# design.net
KiCad netlist of a schematic drawn in Altium Designer
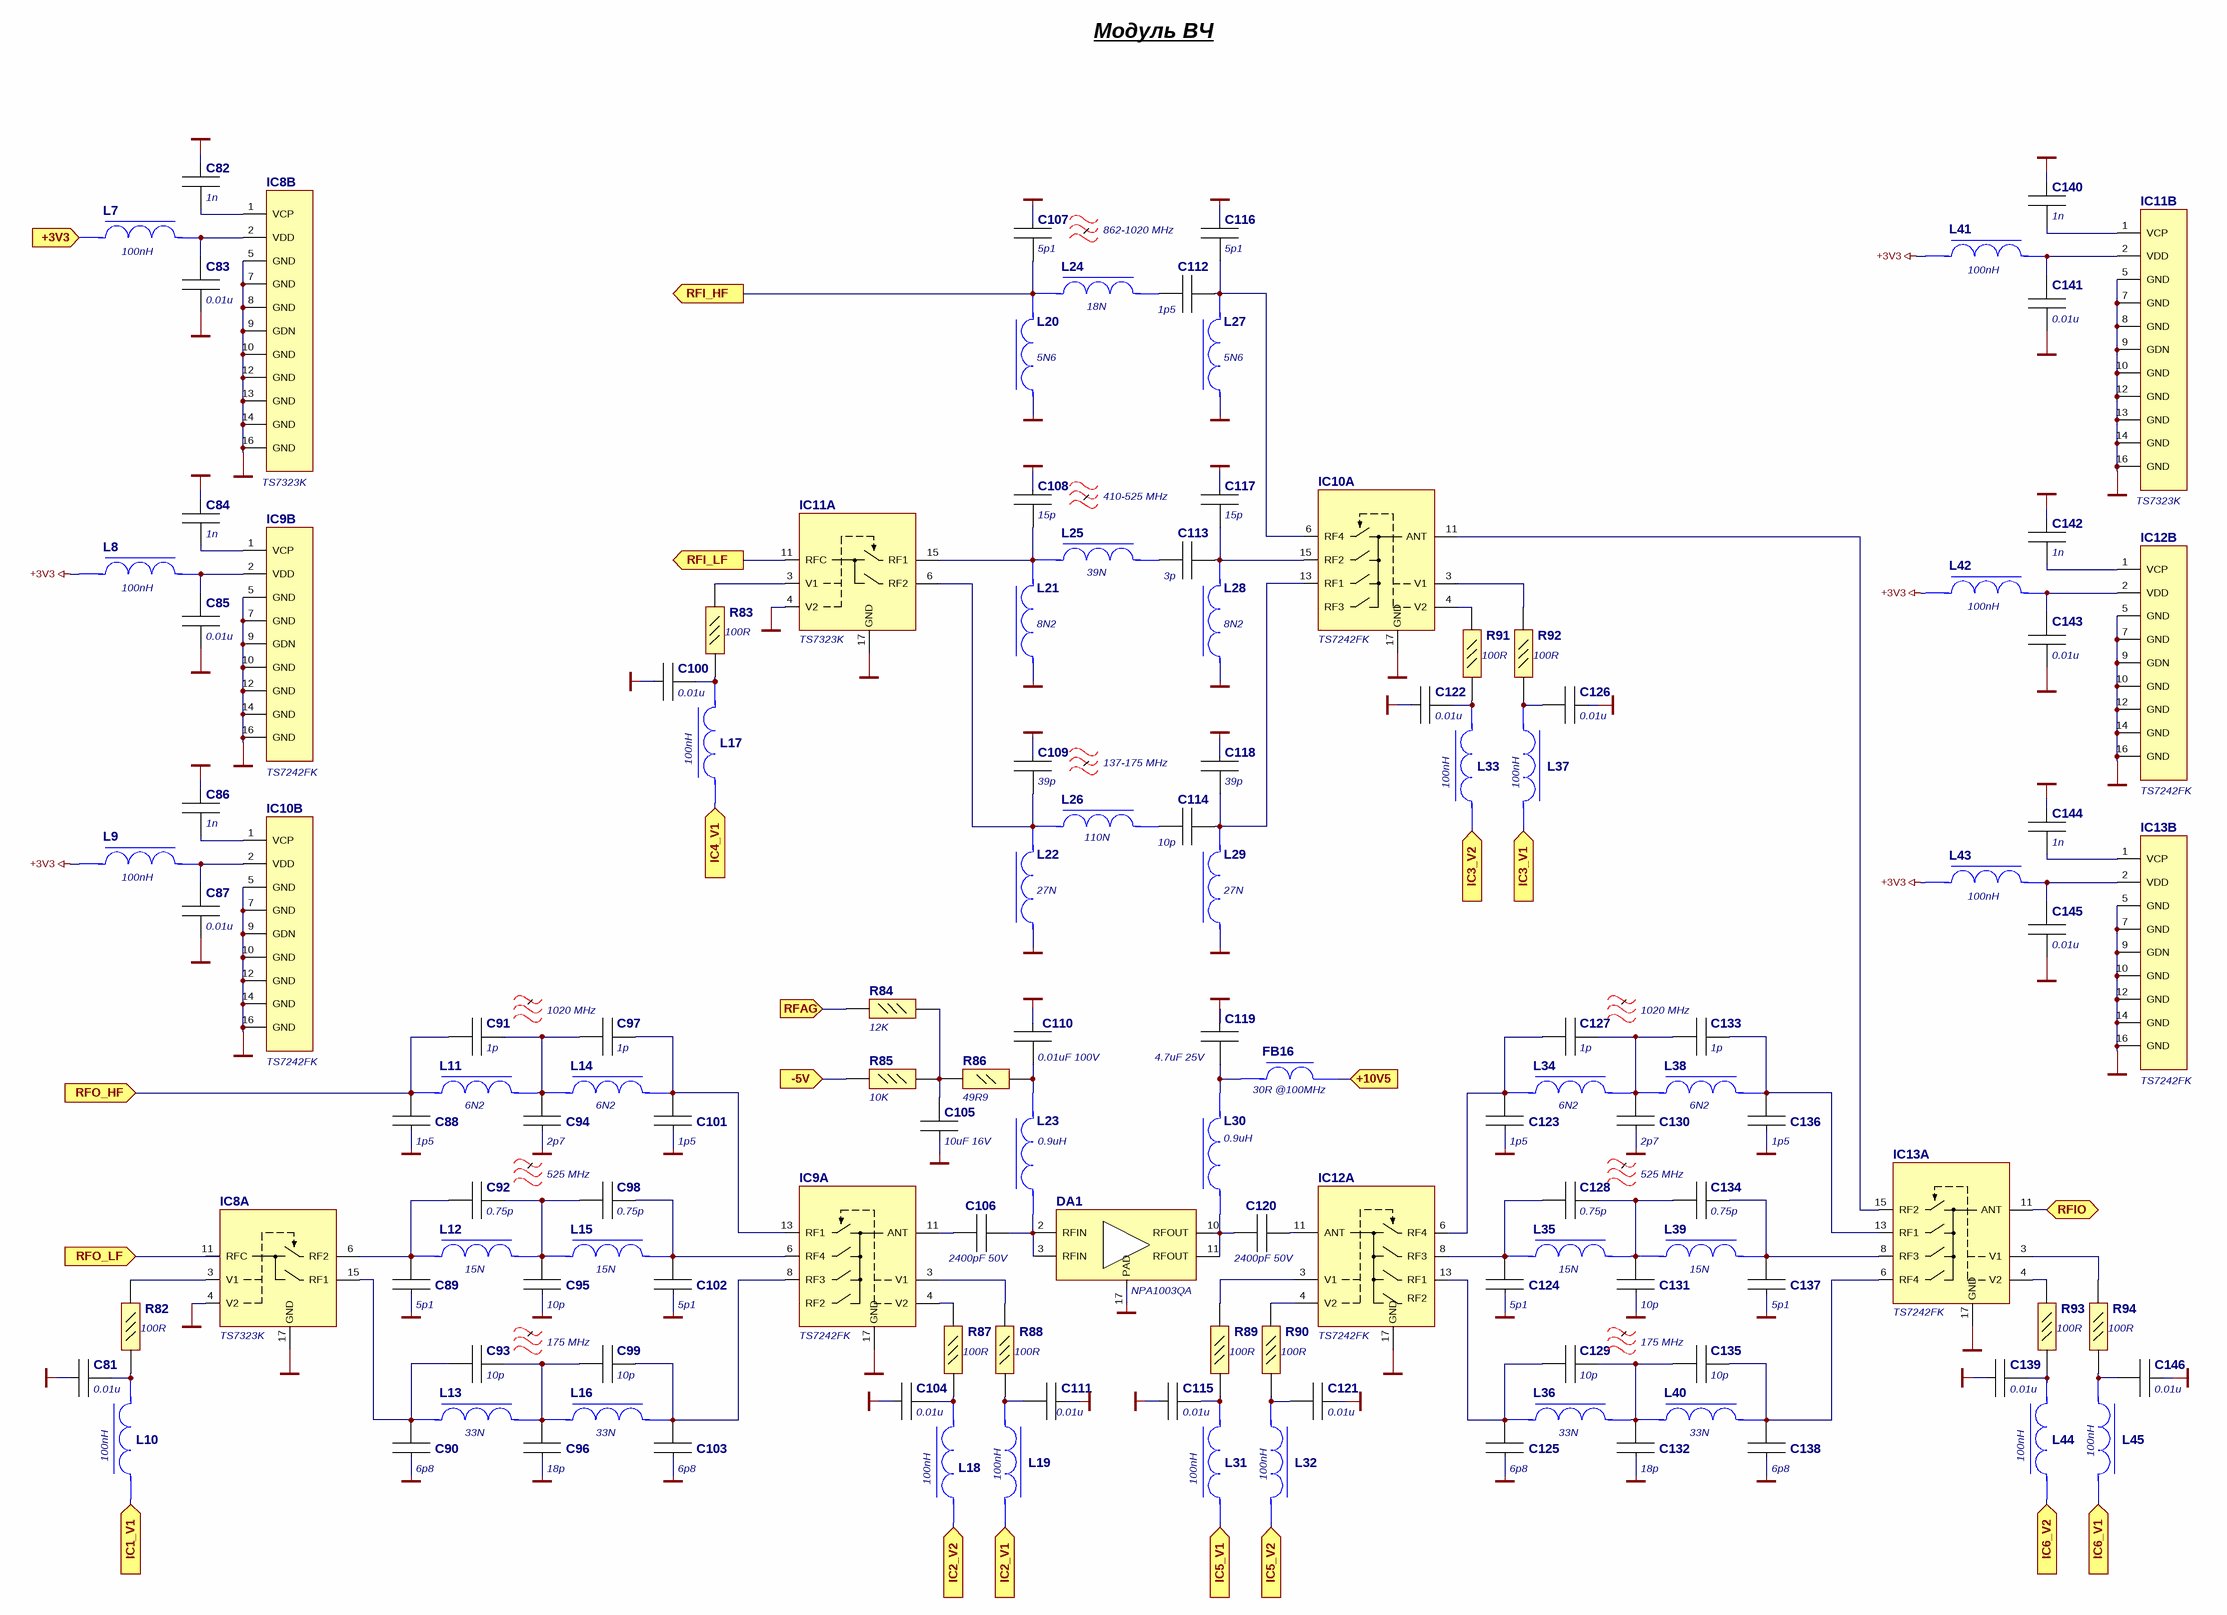
[diagram p0: Модуль ВЧ.SchDoc]

(export (version "E")
  (design (tool "Eeschema 10.0.6"))
  (components
    (comp (ref "C81")
      (value "0.01u")
      (footprint ":CAP0402 100x50x50")
      (description "±5% 35V Ceramic Capacitor C0G, NP0 0402 (1005 Metric)")
      (fields (field (name "MANUFACTURER_PART_NUMBER") "GRM1555CYA103JE01D"))
      (libsource (lib "Capacitors 0402") (part "GRM1555CYA103JE01D"))
    )
    (comp (ref "C82")
      (value "1n")
      (footprint ":CAP0402 100x50x50")
      (description "±5% 50V Ceramic Capacitor C0G, NP0 0402 (1005 Metric)")
      (fields (field (name "MANUFACTURER_PART_NUMBER") "GRM1555C1H102JA01J"))
      (libsource (lib "Capacitors 0402") (part "GRM1555C1H102JA01J"))
    )
    (comp (ref "C83")
      (value "0.01u")
      (footprint ":CAP0402 100x50x50")
      (description "±5% 35V Ceramic Capacitor C0G, NP0 0402 (1005 Metric)")
      (fields (field (name "MANUFACTURER_PART_NUMBER") "GRM1555CYA103JE01D"))
      (libsource (lib "Capacitors 0402") (part "GRM1555CYA103JE01D"))
    )
    (comp (ref "C84")
      (value "1n")
      (footprint ":CAP0402 100x50x50")
      (description "±5% 50V Ceramic Capacitor C0G, NP0 0402 (1005 Metric)")
      (fields (field (name "MANUFACTURER_PART_NUMBER") "GRM1555C1H102JA01J"))
      (libsource (lib "Capacitors 0402") (part "GRM1555C1H102JA01J"))
    )
    (comp (ref "C85")
      (value "0.01u")
      (footprint ":CAP0402 100x50x50")
      (description "±5% 35V Ceramic Capacitor C0G, NP0 0402 (1005 Metric)")
      (fields (field (name "MANUFACTURER_PART_NUMBER") "GRM1555CYA103JE01D"))
      (libsource (lib "Capacitors 0402") (part "GRM1555CYA103JE01D"))
    )
    (comp (ref "C86")
      (value "1n")
      (footprint ":CAP0402 100x50x50")
      (description "±5% 50V Ceramic Capacitor C0G, NP0 0402 (1005 Metric)")
      (fields (field (name "MANUFACTURER_PART_NUMBER") "GRM1555C1H102JA01J"))
      (libsource (lib "Capacitors 0402") (part "GRM1555C1H102JA01J"))
    )
    (comp (ref "C87")
      (value "0.01u")
      (footprint ":CAP0402 100x50x50")
      (description "±5% 35V Ceramic Capacitor C0G, NP0 0402 (1005 Metric)")
      (fields (field (name "MANUFACTURER_PART_NUMBER") "GRM1555CYA103JE01D"))
      (libsource (lib "Capacitors 0402") (part "GRM1555CYA103JE01D"))
    )
    (comp (ref "C88")
      (value "1p5")
      (footprint ":CAP0603 C1608х08")
      (description "Ceramic Capacitor ±0.1pF 250V C0G, NP0 0603 (1608 Metric)")
      (fields (field (name "MANUFACTURER_PART_NUMBER") "GQM1875C2E1R5BB12D"))
      (libsource (lib "Capacitors 0603 ±0.1pF 250V NP0") (part "GQM1875C2E1R5BB12D"))
    )
    (comp (ref "C89")
      (value "5p1")
      (footprint ":CAP0603 C1608х08")
      (description "Ceramic Capacitor ±0.1pF 250V C0G, NP0 0603 (1608 Metric)")
      (fields (field (name "MANUFACTURER_PART_NUMBER") "GQM1875C2E5R1BB12D"))
      (libsource (lib "Capacitors 0603 ±0.1pF 250V NP0") (part "GQM1875C2E5R1BB12D"))
    )
    (comp (ref "C90")
      (value "6p8")
      (footprint ":CAP0603 C1608х08")
      (description "Ceramic Capacitor ±0.1pF 250V C0G, NP0 0603 (1608 Metric)")
      (fields (field (name "MANUFACTURER_PART_NUMBER") "GQM1875C2E6R8BB12D"))
      (libsource (lib "Capacitors 0603 ±0.1pF 250V NP0") (part "GQM1875C2E6R8BB12D"))
    )
    (comp (ref "C91")
      (value "1p")
      (footprint ":CAP0603 C1608х08")
      (description "Ceramic Capacitor ±0.1pF 250V C0G, NP0 0603 (1608 Metric)")
      (fields (field (name "MANUFACTURER_PART_NUMBER") "GQM1875C2E1R0BB12D"))
      (libsource (lib "Capacitors 0603 ±0.1pF 250V NP0") (part "GQM1875C2E1R0BB12D"))
    )
    (comp (ref "C92")
      (value "0.75p")
      (footprint ":CAP0603 C1608х08")
      (description "Ceramic Capacitor ±0.1pF 250V C0G, NP0 0603 (1608 Metric)")
      (fields (field (name "MANUFACTURER_PART_NUMBER") "GQM1875C2ER75BB12D"))
      (libsource (lib "Capacitors 0603 ±0.1pF 250V NP0") (part "GQM1875C2ER75BB12D"))
    )
    (comp (ref "C93")
      (value "10p")
      (footprint ":CAP0603 C1608х08")
      (description "Ceramic Capacitor ±1% 250V C0G, NP0 0603 (1608 Metric)")
      (fields (field (name "MANUFACTURER_PART_NUMBER") "GQM1875C2E100FB12D"))
      (libsource (lib "Capacitors 0603 1% 250V NP0") (part "GQM1875C2E100FB12D"))
    )
    (comp (ref "C94")
      (value "2p7")
      (footprint ":CAP0603 C1608х08")
      (description "Ceramic Capacitor ±0.1pF 250V C0G, NP0 0603 (1608 Metric)")
      (fields (field (name "MANUFACTURER_PART_NUMBER") "GQM1875C2E2R7BB12D"))
      (libsource (lib "Capacitors 0603 ±0.1pF 250V NP0") (part "GQM1875C2E2R7BB12D"))
    )
    (comp (ref "C95")
      (value "10p")
      (footprint ":CAP0603 C1608х08")
      (description "Ceramic Capacitor ±1% 250V C0G, NP0 0603 (1608 Metric)")
      (fields (field (name "MANUFACTURER_PART_NUMBER") "GQM1875C2E100FB12D"))
      (libsource (lib "Capacitors 0603 1% 250V NP0") (part "GQM1875C2E100FB12D"))
    )
    (comp (ref "C96")
      (value "18p")
      (footprint ":CAP0603 C1608х08")
      (description "Ceramic Capacitor ±1% 250V C0G, NP0 0603 (1608 Metric)")
      (fields (field (name "MANUFACTURER_PART_NUMBER") "GQM1875C2E180FB12D"))
      (libsource (lib "Capacitors 0603 1% 250V NP0") (part "GQM1875C2E180FB12D"))
    )
    (comp (ref "C97")
      (value "1p")
      (footprint ":CAP0603 C1608х08")
      (description "Ceramic Capacitor ±0.1pF 250V C0G, NP0 0603 (1608 Metric)")
      (fields (field (name "MANUFACTURER_PART_NUMBER") "GQM1875C2E1R0BB12D"))
      (libsource (lib "Capacitors 0603 ±0.1pF 250V NP0") (part "GQM1875C2E1R0BB12D"))
    )
    (comp (ref "C98")
      (value "0.75p")
      (footprint ":CAP0603 C1608х08")
      (description "Ceramic Capacitor ±0.1pF 250V C0G, NP0 0603 (1608 Metric)")
      (fields (field (name "MANUFACTURER_PART_NUMBER") "GQM1875C2ER75BB12D"))
      (libsource (lib "Capacitors 0603 ±0.1pF 250V NP0") (part "GQM1875C2ER75BB12D"))
    )
    (comp (ref "C99")
      (value "10p")
      (footprint ":CAP0603 C1608х08")
      (description "Ceramic Capacitor ±1% 250V C0G, NP0 0603 (1608 Metric)")
      (fields (field (name "MANUFACTURER_PART_NUMBER") "GQM1875C2E100FB12D"))
      (libsource (lib "Capacitors 0603 1% 250V NP0") (part "GQM1875C2E100FB12D"))
    )
    (comp (ref "C100")
      (value "0.01u")
      (footprint ":CAP0402 100x50x50")
      (description "±5% 35V Ceramic Capacitor C0G, NP0 0402 (1005 Metric)")
      (fields (field (name "MANUFACTURER_PART_NUMBER") "GRM1555CYA103JE01D"))
      (libsource (lib "Capacitors 0402") (part "GRM1555CYA103JE01D"))
    )
    (comp (ref "C101")
      (value "1p5")
      (footprint ":CAP0603 C1608х08")
      (description "Ceramic Capacitor ±0.1pF 250V C0G, NP0 0603 (1608 Metric)")
      (fields (field (name "MANUFACTURER_PART_NUMBER") "GQM1875C2E1R5BB12D"))
      (libsource (lib "Capacitors 0603 ±0.1pF 250V NP0") (part "GQM1875C2E1R5BB12D"))
    )
    (comp (ref "C102")
      (value "5p1")
      (footprint ":CAP0603 C1608х08")
      (description "Ceramic Capacitor ±0.1pF 250V C0G, NP0 0603 (1608 Metric)")
      (fields (field (name "MANUFACTURER_PART_NUMBER") "GQM1875C2E5R1BB12D"))
      (libsource (lib "Capacitors 0603 ±0.1pF 250V NP0") (part "GQM1875C2E5R1BB12D"))
    )
    (comp (ref "C103")
      (value "6p8")
      (footprint ":CAP0603 C1608х08")
      (description "Ceramic Capacitor ±0.1pF 250V C0G, NP0 0603 (1608 Metric)")
      (fields (field (name "MANUFACTURER_PART_NUMBER") "GQM1875C2E6R8BB12D"))
      (libsource (lib "Capacitors 0603 ±0.1pF 250V NP0") (part "GQM1875C2E6R8BB12D"))
    )
    (comp (ref "C104")
      (value "0.01u")
      (footprint ":CAP0402 100x50x50")
      (description "±5% 35V Ceramic Capacitor C0G, NP0 0402 (1005 Metric)")
      (fields (field (name "MANUFACTURER_PART_NUMBER") "GRM1555CYA103JE01D"))
      (libsource (lib "Capacitors 0402") (part "GRM1555CYA103JE01D"))
    )
    (comp (ref "C105")
      (value "10uF 16V")
      (footprint ":CAP0805 C2012X125")
      (description "CAP CER 10uF 16V X5R 0805")
      (fields
        (field (name "MANUFACTURER_PART_NUMBER") "C2012X5R1C106M085AC")
        (field (name "MOUSER PART NUMBER") "810-C2012X5R1C106M-2")
      )
      (libsource (lib "Capacitors 0805") (part "C2012X5R1C106M085AC"))
    )
    (comp (ref "C106")
      (value "2400pF 50V")
      (footprint ":CAP0805 C2012X125")
      (description "2400pF 50V Ceramic Capacitor 0805 (2012 Metric)")
      (fields (field (name "MANUFACTURER_PART_NUMBER") "C08BL242X-5UN-X0T"))
      (libsource (lib "Capacitors 0805") (part "C08BL242X-5UN-X0T"))
    )
    (comp (ref "C107")
      (value "5p1")
      (footprint ":CAP0603 C1608х08")
      (description "Ceramic Capacitor ±0.1pF 250V C0G, NP0 0603 (1608 Metric)")
      (fields (field (name "MANUFACTURER_PART_NUMBER") "GQM1875C2E5R1BB12D"))
      (libsource (lib "Capacitors 0603 ±0.1pF 250V NP0") (part "GQM1875C2E5R1BB12D"))
    )
    (comp (ref "C108")
      (value "15p")
      (footprint ":CAP0603 C1608х08")
      (description "Ceramic Capacitor ±1% 250V C0G, NP0 0603 (1608 Metric)")
      (fields (field (name "MANUFACTURER_PART_NUMBER") "GQM1875C2E150FB12D"))
      (libsource (lib "Capacitors 0603 1% 250V NP0") (part "GQM1875C2E150FB12D"))
    )
    (comp (ref "C109")
      (value "39p")
      (footprint ":CAP0603 C1608х08")
      (description "Ceramic Capacitor ±1% 250V C0G, NP0 0603 (1608 Metric)")
      (fields (field (name "MANUFACTURER_PART_NUMBER") "GQM1875C2E390FB12D"))
      (libsource (lib "Capacitors 0603 1% 250V NP0") (part "GQM1875C2E390FB12D"))
    )
    (comp (ref "C110")
      (value "0.01uF 100V")
      (footprint ":CAP0603 C1608х08")
      (description "CAP CER 0.01uF 100V X7R 0603")
      (fields
        (field (name "MANUFACTURER_PART_NUMBER") "06031C103JAT2A")
        (field (name "MOUSER PART NUMBER") "581-06031C103J")
      )
      (libsource (lib "Capacitors 0603") (part "06031C103JAT2A"))
    )
    (comp (ref "C111")
      (value "0.01u")
      (footprint ":CAP0402 100x50x50")
      (description "±5% 35V Ceramic Capacitor C0G, NP0 0402 (1005 Metric)")
      (fields (field (name "MANUFACTURER_PART_NUMBER") "GRM1555CYA103JE01D"))
      (libsource (lib "Capacitors 0402") (part "GRM1555CYA103JE01D"))
    )
    (comp (ref "C112")
      (value "1p5")
      (footprint ":CAP0603 C1608х08")
      (description "Ceramic Capacitor ±0.1pF 250V C0G, NP0 0603 (1608 Metric)")
      (fields (field (name "MANUFACTURER_PART_NUMBER") "GQM1875C2E1R5BB12D"))
      (libsource (lib "Capacitors 0603 ±0.1pF 250V NP0") (part "GQM1875C2E1R5BB12D"))
    )
    (comp (ref "C113")
      (value "3p")
      (footprint ":CAP0603 C1608х08")
      (description "Ceramic Capacitor ±0.1pF 250V C0G, NP0 0603 (1608 Metric)")
      (fields (field (name "MANUFACTURER_PART_NUMBER") "GQM1875C2E3R0BB12D"))
      (libsource (lib "Capacitors 0603 ±0.1pF 250V NP0") (part "GQM1875C2E3R0BB12D"))
    )
    (comp (ref "C114")
      (value "10p")
      (footprint ":CAP0603 C1608х08")
      (description "Ceramic Capacitor ±1% 250V C0G, NP0 0603 (1608 Metric)")
      (fields (field (name "MANUFACTURER_PART_NUMBER") "GQM1875C2E100FB12D"))
      (libsource (lib "Capacitors 0603 1% 250V NP0") (part "GQM1875C2E100FB12D"))
    )
    (comp (ref "C115")
      (value "0.01u")
      (footprint ":CAP0402 100x50x50")
      (description "±5% 35V Ceramic Capacitor C0G, NP0 0402 (1005 Metric)")
      (fields (field (name "MANUFACTURER_PART_NUMBER") "GRM1555CYA103JE01D"))
      (libsource (lib "Capacitors 0402") (part "GRM1555CYA103JE01D"))
    )
    (comp (ref "C116")
      (value "5p1")
      (footprint ":CAP0603 C1608х08")
      (description "Ceramic Capacitor ±0.1pF 250V C0G, NP0 0603 (1608 Metric)")
      (fields (field (name "MANUFACTURER_PART_NUMBER") "GQM1875C2E5R1BB12D"))
      (libsource (lib "Capacitors 0603 ±0.1pF 250V NP0") (part "GQM1875C2E5R1BB12D"))
    )
    (comp (ref "C117")
      (value "15p")
      (footprint ":CAP0603 C1608х08")
      (description "Ceramic Capacitor ±1% 250V C0G, NP0 0603 (1608 Metric)")
      (fields (field (name "MANUFACTURER_PART_NUMBER") "GQM1875C2E150FB12D"))
      (libsource (lib "Capacitors 0603 1% 250V NP0") (part "GQM1875C2E150FB12D"))
    )
    (comp (ref "C118")
      (value "39p")
      (footprint ":CAP0603 C1608х08")
      (description "Ceramic Capacitor ±1% 250V C0G, NP0 0603 (1608 Metric)")
      (fields (field (name "MANUFACTURER_PART_NUMBER") "GQM1875C2E390FB12D"))
      (libsource (lib "Capacitors 0603 1% 250V NP0") (part "GQM1875C2E390FB12D"))
    )
    (comp (ref "C119")
      (value "4.7uF 25V")
      (footprint ":CAP0805 C2012X125")
      (description "CAP CER 4.7uF 25V X7R 0805")
      (fields (field (name "MANUFACTURER_PART_NUMBER") "GRM21BZ71E475KE15L"))
      (libsource (lib "Capacitors 0805") (part "GRM21BZ71E475KE15L"))
    )
    (comp (ref "C120")
      (value "2400pF 50V")
      (footprint ":CAP0805 C2012X125")
      (description "2400pF 50V Ceramic Capacitor 0805 (2012 Metric)")
      (fields (field (name "MANUFACTURER_PART_NUMBER") "C08BL242X-5UN-X0T"))
      (libsource (lib "Capacitors 0805") (part "C08BL242X-5UN-X0T"))
    )
    (comp (ref "C121")
      (value "0.01u")
      (footprint ":CAP0402 100x50x50")
      (description "±5% 35V Ceramic Capacitor C0G, NP0 0402 (1005 Metric)")
      (fields (field (name "MANUFACTURER_PART_NUMBER") "GRM1555CYA103JE01D"))
      (libsource (lib "Capacitors 0402") (part "GRM1555CYA103JE01D"))
    )
    (comp (ref "C122")
      (value "0.01u")
      (footprint ":CAP0402 100x50x50")
      (description "±5% 35V Ceramic Capacitor C0G, NP0 0402 (1005 Metric)")
      (fields (field (name "MANUFACTURER_PART_NUMBER") "GRM1555CYA103JE01D"))
      (libsource (lib "Capacitors 0402") (part "GRM1555CYA103JE01D"))
    )
    (comp (ref "C123")
      (value "1p5")
      (footprint ":CAP0603 C1608х08")
      (description "Ceramic Capacitor ±0.1pF 250V C0G, NP0 0603 (1608 Metric)")
      (fields (field (name "MANUFACTURER_PART_NUMBER") "GQM1875C2E1R5BB12D"))
      (libsource (lib "Capacitors 0603 ±0.1pF 250V NP0") (part "GQM1875C2E1R5BB12D"))
    )
    (comp (ref "C124")
      (value "5p1")
      (footprint ":CAP0603 C1608х08")
      (description "Ceramic Capacitor ±0.1pF 250V C0G, NP0 0603 (1608 Metric)")
      (fields (field (name "MANUFACTURER_PART_NUMBER") "GQM1875C2E5R1BB12D"))
      (libsource (lib "Capacitors 0603 ±0.1pF 250V NP0") (part "GQM1875C2E5R1BB12D"))
    )
    (comp (ref "C125")
      (value "6p8")
      (footprint ":CAP0603 C1608х08")
      (description "Ceramic Capacitor ±0.1pF 250V C0G, NP0 0603 (1608 Metric)")
      (fields (field (name "MANUFACTURER_PART_NUMBER") "GQM1875C2E6R8BB12D"))
      (libsource (lib "Capacitors 0603 ±0.1pF 250V NP0") (part "GQM1875C2E6R8BB12D"))
    )
    (comp (ref "C126")
      (value "0.01u")
      (footprint ":CAP0402 100x50x50")
      (description "±5% 35V Ceramic Capacitor C0G, NP0 0402 (1005 Metric)")
      (fields (field (name "MANUFACTURER_PART_NUMBER") "GRM1555CYA103JE01D"))
      (libsource (lib "Capacitors 0402") (part "GRM1555CYA103JE01D"))
    )
    (comp (ref "C127")
      (value "1p")
      (footprint ":CAP0603 C1608х08")
      (description "Ceramic Capacitor ±0.1pF 250V C0G, NP0 0603 (1608 Metric)")
      (fields (field (name "MANUFACTURER_PART_NUMBER") "GQM1875C2E1R0BB12D"))
      (libsource (lib "Capacitors 0603 ±0.1pF 250V NP0") (part "GQM1875C2E1R0BB12D"))
    )
    (comp (ref "C128")
      (value "0.75p")
      (footprint ":CAP0603 C1608х08")
      (description "Ceramic Capacitor ±0.1pF 250V C0G, NP0 0603 (1608 Metric)")
      (fields (field (name "MANUFACTURER_PART_NUMBER") "GQM1875C2ER75BB12D"))
      (libsource (lib "Capacitors 0603 ±0.1pF 250V NP0") (part "GQM1875C2ER75BB12D"))
    )
    (comp (ref "C129")
      (value "10p")
      (footprint ":CAP0603 C1608х08")
      (description "Ceramic Capacitor ±1% 250V C0G, NP0 0603 (1608 Metric)")
      (fields (field (name "MANUFACTURER_PART_NUMBER") "GQM1875C2E100FB12D"))
      (libsource (lib "Capacitors 0603 1% 250V NP0") (part "GQM1875C2E100FB12D"))
    )
    (comp (ref "C130")
      (value "2p7")
      (footprint ":CAP0603 C1608х08")
      (description "Ceramic Capacitor ±0.1pF 250V C0G, NP0 0603 (1608 Metric)")
      (fields (field (name "MANUFACTURER_PART_NUMBER") "GQM1875C2E2R7BB12D"))
      (libsource (lib "Capacitors 0603 ±0.1pF 250V NP0") (part "GQM1875C2E2R7BB12D"))
    )
    (comp (ref "C131")
      (value "10p")
      (footprint ":CAP0603 C1608х08")
      (description "Ceramic Capacitor ±1% 250V C0G, NP0 0603 (1608 Metric)")
      (fields (field (name "MANUFACTURER_PART_NUMBER") "GQM1875C2E100FB12D"))
      (libsource (lib "Capacitors 0603 1% 250V NP0") (part "GQM1875C2E100FB12D"))
    )
    (comp (ref "C132")
      (value "18p")
      (footprint ":CAP0603 C1608х08")
      (description "Ceramic Capacitor ±1% 250V C0G, NP0 0603 (1608 Metric)")
      (fields (field (name "MANUFACTURER_PART_NUMBER") "GQM1875C2E180FB12D"))
      (libsource (lib "Capacitors 0603 1% 250V NP0") (part "GQM1875C2E180FB12D"))
    )
    (comp (ref "C133")
      (value "1p")
      (footprint ":CAP0603 C1608х08")
      (description "Ceramic Capacitor ±0.1pF 250V C0G, NP0 0603 (1608 Metric)")
      (fields (field (name "MANUFACTURER_PART_NUMBER") "GQM1875C2E1R0BB12D"))
      (libsource (lib "Capacitors 0603 ±0.1pF 250V NP0") (part "GQM1875C2E1R0BB12D"))
    )
    (comp (ref "C134")
      (value "0.75p")
      (footprint ":CAP0603 C1608х08")
      (description "Ceramic Capacitor ±0.1pF 250V C0G, NP0 0603 (1608 Metric)")
      (fields (field (name "MANUFACTURER_PART_NUMBER") "GQM1875C2ER75BB12D"))
      (libsource (lib "Capacitors 0603 ±0.1pF 250V NP0") (part "GQM1875C2ER75BB12D"))
    )
    (comp (ref "C135")
      (value "10p")
      (footprint ":CAP0603 C1608х08")
      (description "Ceramic Capacitor ±1% 250V C0G, NP0 0603 (1608 Metric)")
      (fields (field (name "MANUFACTURER_PART_NUMBER") "GQM1875C2E100FB12D"))
      (libsource (lib "Capacitors 0603 1% 250V NP0") (part "GQM1875C2E100FB12D"))
    )
    (comp (ref "C136")
      (value "1p5")
      (footprint ":CAP0603 C1608х08")
      (description "Ceramic Capacitor ±0.1pF 250V C0G, NP0 0603 (1608 Metric)")
      (fields (field (name "MANUFACTURER_PART_NUMBER") "GQM1875C2E1R5BB12D"))
      (libsource (lib "Capacitors 0603 ±0.1pF 250V NP0") (part "GQM1875C2E1R5BB12D"))
    )
    (comp (ref "C137")
      (value "5p1")
      (footprint ":CAP0603 C1608х08")
      (description "Ceramic Capacitor ±0.1pF 250V C0G, NP0 0603 (1608 Metric)")
      (fields (field (name "MANUFACTURER_PART_NUMBER") "GQM1875C2E5R1BB12D"))
      (libsource (lib "Capacitors 0603 ±0.1pF 250V NP0") (part "GQM1875C2E5R1BB12D"))
    )
    (comp (ref "C138")
      (value "6p8")
      (footprint ":CAP0603 C1608х08")
      (description "Ceramic Capacitor ±0.1pF 250V C0G, NP0 0603 (1608 Metric)")
      (fields (field (name "MANUFACTURER_PART_NUMBER") "GQM1875C2E6R8BB12D"))
      (libsource (lib "Capacitors 0603 ±0.1pF 250V NP0") (part "GQM1875C2E6R8BB12D"))
    )
    (comp (ref "C139")
      (value "0.01u")
      (footprint ":CAP0402 100x50x50")
      (description "±5% 35V Ceramic Capacitor C0G, NP0 0402 (1005 Metric)")
      (fields (field (name "MANUFACTURER_PART_NUMBER") "GRM1555CYA103JE01D"))
      (libsource (lib "Capacitors 0402") (part "GRM1555CYA103JE01D"))
    )
    (comp (ref "C140")
      (value "1n")
      (footprint ":CAP0402 100x50x50")
      (description "±5% 50V Ceramic Capacitor C0G, NP0 0402 (1005 Metric)")
      (fields (field (name "MANUFACTURER_PART_NUMBER") "GRM1555C1H102JA01J"))
      (libsource (lib "Capacitors 0402") (part "GRM1555C1H102JA01J"))
    )
    (comp (ref "C141")
      (value "0.01u")
      (footprint ":CAP0402 100x50x50")
      (description "±5% 35V Ceramic Capacitor C0G, NP0 0402 (1005 Metric)")
      (fields (field (name "MANUFACTURER_PART_NUMBER") "GRM1555CYA103JE01D"))
      (libsource (lib "Capacitors 0402") (part "GRM1555CYA103JE01D"))
    )
    (comp (ref "C142")
      (value "1n")
      (footprint ":CAP0402 100x50x50")
      (description "±5% 50V Ceramic Capacitor C0G, NP0 0402 (1005 Metric)")
      (fields (field (name "MANUFACTURER_PART_NUMBER") "GRM1555C1H102JA01J"))
      (libsource (lib "Capacitors 0402") (part "GRM1555C1H102JA01J"))
    )
    (comp (ref "C143")
      (value "0.01u")
      (footprint ":CAP0402 100x50x50")
      (description "±5% 35V Ceramic Capacitor C0G, NP0 0402 (1005 Metric)")
      (fields (field (name "MANUFACTURER_PART_NUMBER") "GRM1555CYA103JE01D"))
      (libsource (lib "Capacitors 0402") (part "GRM1555CYA103JE01D"))
    )
    (comp (ref "C144")
      (value "1n")
      (footprint ":CAP0402 100x50x50")
      (description "±5% 50V Ceramic Capacitor C0G, NP0 0402 (1005 Metric)")
      (fields (field (name "MANUFACTURER_PART_NUMBER") "GRM1555C1H102JA01J"))
      (libsource (lib "Capacitors 0402") (part "GRM1555C1H102JA01J"))
    )
    (comp (ref "C145")
      (value "0.01u")
      (footprint ":CAP0402 100x50x50")
      (description "±5% 35V Ceramic Capacitor C0G, NP0 0402 (1005 Metric)")
      (fields (field (name "MANUFACTURER_PART_NUMBER") "GRM1555CYA103JE01D"))
      (libsource (lib "Capacitors 0402") (part "GRM1555CYA103JE01D"))
    )
    (comp (ref "C146")
      (value "0.01u")
      (footprint ":CAP0402 100x50x50")
      (description "±5% 35V Ceramic Capacitor C0G, NP0 0402 (1005 Metric)")
      (fields (field (name "MANUFACTURER_PART_NUMBER") "GRM1555CYA103JE01D"))
      (libsource (lib "Capacitors 0402") (part "GRM1555CYA103JE01D"))
    )
    (comp (ref "DA1")
      (value "NPA1003QA")
      (footprint ":QFN16 P400X400X95-17N-D")
      (description "GaN 20 - 1500 MHz Power Amplifier 16dB 5W")
      (fields (field (name "MOUSER PART NUMBER") "937-NPA1003QA"))
      (libsource (lib "Analog ICs") (part "NPA1003QA"))
    )
    (comp (ref "FB16")
      (value "30R @100MHz")
      (footprint ":FER BLM18SP300SN1D")
      (description "30 Ohms @ 100MHz 1 Power Line Ferrite Bead 0603 (1608 Metric) 6A 8mOhm")
      (fields
        (field (name "MANUFACTURER_PART_NUMBER") "BLM18SP300SN1D")
        (field (name "MOUSER PART NUMBER") "81-BLM18SP300SN1D")
      )
      (libsource (lib "Ferrite Bead") (part "BLM18SP300SN1D"))
    )
    (comp (ref "IC8")
      (value "TS7323K")
      (footprint ":QFN16 P300X300X80-17N-D")
      (description "SPDT Switch 1MHz to 1GHz")
      (fields (field (name "MANUFACTURER_PART_NUMBER") "TS7323KMTRPBF"))
      (libsource (lib "") (part "TS7323K_1"))
    )
    (comp (ref "IC9")
      (value "TS7242FK")
      (footprint ":QFN16 P300X300X80-17N-D")
      (description "SP4T Switch 10MHz to 3GHz")
      (fields (field (name "MANUFACTURER_PART_NUMBER") "TS7242FKMTRPBF"))
      (libsource (lib "") (part "TS7242FK_1"))
    )
    (comp (ref "IC10")
      (value "TS7242FK")
      (footprint ":QFN16 P300X300X80-17N-D")
      (description "SP4T Switch 10MHz to 3GHz")
      (fields (field (name "MANUFACTURER_PART_NUMBER") "TS7242FKMTRPBF"))
      (libsource (lib "") (part "TS7242FK_4"))
    )
    (comp (ref "IC11")
      (value "TS7323K")
      (footprint ":QFN16 P300X300X80-17N-D")
      (description "SPDT Switch 1MHz to 1GHz")
      (fields (field (name "MANUFACTURER_PART_NUMBER") "TS7323KMTRPBF"))
      (libsource (lib "") (part "TS7323K_1"))
    )
    (comp (ref "IC12")
      (value "TS7242FK")
      (footprint ":QFN16 P300X300X80-17N-D")
      (description "SP4T Switch 10MHz to 3GHz")
      (fields (field (name "MANUFACTURER_PART_NUMBER") "TS7242FKMTRPBF"))
      (libsource (lib "") (part "TS7242FK_3"))
    )
    (comp (ref "IC13")
      (value "TS7242FK")
      (footprint ":QFN16 P300X300X80-17N-D")
      (description "SP4T Switch 10MHz to 3GHz")
      (fields (field (name "MANUFACTURER_PART_NUMBER") "TS7242FKMTRPBF"))
      (libsource (lib "") (part "TS7242FK_2"))
    )
    (comp (ref "L7")
      (value "100nH")
      (footprint ":IND 0402")
      (description "Unshielded Multilayer Inductor 0402 5%")
      (fields (field (name "MANUFACTURER_PART_NUMBER") "LQG15HNR10J02D"))
      (libsource (lib "Inductance 0402") (part "LQG15HNR10J02D"))
    )
    (comp (ref "L8")
      (value "100nH")
      (footprint ":IND 0402")
      (description "Unshielded Multilayer Inductor 0402 5%")
      (fields (field (name "MANUFACTURER_PART_NUMBER") "LQG15HNR10J02D"))
      (libsource (lib "Inductance 0402") (part "LQG15HNR10J02D"))
    )
    (comp (ref "L9")
      (value "100nH")
      (footprint ":IND 0402")
      (description "Unshielded Multilayer Inductor 0402 5%")
      (fields (field (name "MANUFACTURER_PART_NUMBER") "LQG15HNR10J02D"))
      (libsource (lib "Inductance 0402") (part "LQG15HNR10J02D"))
    )
    (comp (ref "L10")
      (value "100nH")
      (footprint ":IND 0402")
      (description "Unshielded Multilayer Inductor 0402 5%")
      (fields (field (name "MANUFACTURER_PART_NUMBER") "LQG15HNR10J02D"))
      (libsource (lib "Inductance 0402") (part "LQG15HNR10J02D"))
    )
    (comp (ref "L11")
      (value "~")
      (footprint ":IND 0603 (1608)")
      (fields
        (field (name "MANUFACTURER_PART_NUMBER") "LQW18AN")
        (field (name "MANUFACTURER_PART_NUMBER (PART 2: VALUE)") "6N2")
      )
      (libsource (lib "Inductance 0603") (part "LQW18AN...G8ZD"))
    )
    (comp (ref "L12")
      (value "LQW18AN...G8ZD")
      (footprint ":IND 0603 (1608)")
      (fields
        (field (name "MANUFACTURER_PART_NUMBER") "LQW18AN")
        (field (name "MANUFACTURER_PART_NUMBER (PART 2: VALUE)") "15N")
      )
      (libsource (lib "Inductance 0603") (part "LQW18AN...G8ZD"))
    )
    (comp (ref "L13")
      (value "LQW18AN...G8ZD")
      (footprint ":IND 0603 (1608)")
      (fields
        (field (name "MANUFACTURER_PART_NUMBER") "LQW18AN")
        (field (name "MANUFACTURER_PART_NUMBER (PART 2: VALUE)") "33N")
      )
      (libsource (lib "Inductance 0603") (part "LQW18AN...G8ZD"))
    )
    (comp (ref "L14")
      (value "LQW18AN...G8ZD")
      (footprint ":IND 0603 (1608)")
      (fields
        (field (name "MANUFACTURER_PART_NUMBER") "LQW18AN")
        (field (name "MANUFACTURER_PART_NUMBER (PART 2: VALUE)") "6N2")
      )
      (libsource (lib "Inductance 0603") (part "LQW18AN...G8ZD"))
    )
    (comp (ref "L15")
      (value "LQW18AN...G8ZD")
      (footprint ":IND 0603 (1608)")
      (fields
        (field (name "MANUFACTURER_PART_NUMBER") "LQW18AN")
        (field (name "MANUFACTURER_PART_NUMBER (PART 2: VALUE)") "15N")
      )
      (libsource (lib "Inductance 0603") (part "LQW18AN...G8ZD"))
    )
    (comp (ref "L16")
      (value "LQW18AN...G8ZD")
      (footprint ":IND 0603 (1608)")
      (fields
        (field (name "MANUFACTURER_PART_NUMBER") "LQW18AN")
        (field (name "MANUFACTURER_PART_NUMBER (PART 2: VALUE)") "33N")
      )
      (libsource (lib "Inductance 0603") (part "LQW18AN...G8ZD"))
    )
    (comp (ref "L17")
      (value "100nH")
      (footprint ":IND 0402")
      (description "Unshielded Multilayer Inductor 0402 5%")
      (fields (field (name "MANUFACTURER_PART_NUMBER") "LQG15HNR10J02D"))
      (libsource (lib "Inductance 0402") (part "LQG15HNR10J02D"))
    )
    (comp (ref "L18")
      (value "100nH")
      (footprint ":IND 0402")
      (description "Unshielded Multilayer Inductor 0402 5%")
      (fields (field (name "MANUFACTURER_PART_NUMBER") "LQG15HNR10J02D"))
      (libsource (lib "Inductance 0402") (part "LQG15HNR10J02D"))
    )
    (comp (ref "L19")
      (value "100nH")
      (footprint ":IND 0402")
      (description "Unshielded Multilayer Inductor 0402 5%")
      (fields (field (name "MANUFACTURER_PART_NUMBER") "LQG15HNR10J02D"))
      (libsource (lib "") (part "LQG15HNR10J02D_1"))
    )
    (comp (ref "L20")
      (value "~")
      (footprint ":IND 0603 (1608)")
      (fields
        (field (name "MANUFACTURER_PART_NUMBER") "LQW18AN")
        (field (name "MANUFACTURER_PART_NUMBER (PART 2: VALUE)") "5N6")
      )
      (libsource (lib "Inductance 0603") (part "LQW18AN...G8ZD"))
    )
    (comp (ref "L21")
      (value "LQW18AN...G8ZD")
      (footprint ":IND 0603 (1608)")
      (fields
        (field (name "MANUFACTURER_PART_NUMBER") "LQW18AN")
        (field (name "MANUFACTURER_PART_NUMBER (PART 2: VALUE)") "8N2")
      )
      (libsource (lib "Inductance 0603") (part "LQW18AN...G8ZD"))
    )
    (comp (ref "L22")
      (value "LQW18AN...G8ZD")
      (footprint ":IND 0603 (1608)")
      (fields
        (field (name "MANUFACTURER_PART_NUMBER") "LQW18AN")
        (field (name "MANUFACTURER_PART_NUMBER (PART 2: VALUE)") "27N")
      )
      (libsource (lib "Inductance 0603") (part "LQW18AN...G8ZD"))
    )
    (comp (ref "L23")
      (value "0.9uH")
      (footprint ":IND 1008AF901XJLC")
      (fields (field (name "MANUFACTURER_PART_NUMBER") "1008AF-901XJLC"))
      (libsource (lib "Inductance") (part "1008AF-901XJLC"))
    )
    (comp (ref "L24")
      (value "LQW18AN...G8ZD")
      (footprint ":IND 0603 (1608)")
      (fields
        (field (name "MANUFACTURER_PART_NUMBER") "LQW18AN")
        (field (name "MANUFACTURER_PART_NUMBER (PART 2: VALUE)") "18N")
      )
      (libsource (lib "Inductance 0603") (part "LQW18AN...G8ZD"))
    )
    (comp (ref "L25")
      (value "LQW18AN...G8ZD")
      (footprint ":IND 0603 (1608)")
      (fields
        (field (name "MANUFACTURER_PART_NUMBER") "LQW18AN")
        (field (name "MANUFACTURER_PART_NUMBER (PART 2: VALUE)") "39N")
      )
      (libsource (lib "Inductance 0603") (part "LQW18AN...G8ZD"))
    )
    (comp (ref "L26")
      (value "110N")
      (footprint ":IND 0603 (1608)")
      (fields (field (name "MANUFACTURER_PART_NUMBER") "LQW18AN"))
      (libsource (lib "Inductance 0603") (part "LQW18AN...G8ZD"))
    )
    (comp (ref "L27")
      (value "LQW18AN...G8ZD")
      (footprint ":IND 0603 (1608)")
      (fields
        (field (name "MANUFACTURER_PART_NUMBER") "LQW18AN")
        (field (name "MANUFACTURER_PART_NUMBER (PART 2: VALUE)") "5N6")
      )
      (libsource (lib "Inductance 0603") (part "LQW18AN...G8ZD"))
    )
    (comp (ref "L28")
      (value "LQW18AN...G8ZD")
      (footprint ":IND 0603 (1608)")
      (fields
        (field (name "MANUFACTURER_PART_NUMBER") "LQW18AN")
        (field (name "MANUFACTURER_PART_NUMBER (PART 2: VALUE)") "8N2")
      )
      (libsource (lib "Inductance 0603") (part "LQW18AN...G8ZD"))
    )
    (comp (ref "L29")
      (value "LQW18AN...G8ZD")
      (footprint ":IND 0603 (1608)")
      (fields
        (field (name "MANUFACTURER_PART_NUMBER") "LQW18AN")
        (field (name "MANUFACTURER_PART_NUMBER (PART 2: VALUE)") "27N")
      )
      (libsource (lib "Inductance 0603") (part "LQW18AN...G8ZD"))
    )
    (comp (ref "L30")
      (value "0.9uH")
      (footprint ":IND 1008AF901XJLC")
      (fields (field (name "MANUFACTURER_PART_NUMBER") "1008AF-901XJLC"))
      (libsource (lib "Inductance") (part "1008AF-901XJLC"))
    )
    (comp (ref "L31")
      (value "100nH")
      (footprint ":IND 0402")
      (description "Unshielded Multilayer Inductor 0402 5%")
      (fields (field (name "MANUFACTURER_PART_NUMBER") "LQG15HNR10J02D"))
      (libsource (lib "Inductance 0402") (part "LQG15HNR10J02D"))
    )
    (comp (ref "L32")
      (value "100nH")
      (footprint ":IND 0402")
      (description "Unshielded Multilayer Inductor 0402 5%")
      (fields (field (name "MANUFACTURER_PART_NUMBER") "LQG15HNR10J02D"))
      (libsource (lib "") (part "LQG15HNR10J02D_1"))
    )
    (comp (ref "L33")
      (value "100nH")
      (footprint ":IND 0402")
      (description "Unshielded Multilayer Inductor 0402 5%")
      (fields (field (name "MANUFACTURER_PART_NUMBER") "LQG15HNR10J02D"))
      (libsource (lib "Inductance 0402") (part "LQG15HNR10J02D"))
    )
    (comp (ref "L34")
      (value "LQW18AN...G8ZD")
      (footprint ":IND 0603 (1608)")
      (fields
        (field (name "MANUFACTURER_PART_NUMBER") "LQW18AN")
        (field (name "MANUFACTURER_PART_NUMBER (PART 2: VALUE)") "6N2")
      )
      (libsource (lib "Inductance 0603") (part "LQW18AN...G8ZD"))
    )
    (comp (ref "L35")
      (value "LQW18AN...G8ZD")
      (footprint ":IND 0603 (1608)")
      (fields
        (field (name "MANUFACTURER_PART_NUMBER") "LQW18AN")
        (field (name "MANUFACTURER_PART_NUMBER (PART 2: VALUE)") "15N")
      )
      (libsource (lib "Inductance 0603") (part "LQW18AN...G8ZD"))
    )
    (comp (ref "L36")
      (value "LQW18AN...G8ZD")
      (footprint ":IND 0603 (1608)")
      (fields
        (field (name "MANUFACTURER_PART_NUMBER") "LQW18AN")
        (field (name "MANUFACTURER_PART_NUMBER (PART 2: VALUE)") "33N")
      )
      (libsource (lib "Inductance 0603") (part "LQW18AN...G8ZD"))
    )
    (comp (ref "L37")
      (value "100nH")
      (footprint ":IND 0402")
      (description "Unshielded Multilayer Inductor 0402 5%")
      (fields (field (name "MANUFACTURER_PART_NUMBER") "LQG15HNR10J02D"))
      (libsource (lib "") (part "LQG15HNR10J02D_1"))
    )
    (comp (ref "L38")
      (value "LQW18AN...G8ZD")
      (footprint ":IND 0603 (1608)")
      (fields
        (field (name "MANUFACTURER_PART_NUMBER") "LQW18AN")
        (field (name "MANUFACTURER_PART_NUMBER (PART 2: VALUE)") "6N2")
      )
      (libsource (lib "Inductance 0603") (part "LQW18AN...G8ZD"))
    )
    (comp (ref "L39")
      (value "LQW18AN...G8ZD")
      (footprint ":IND 0603 (1608)")
      (fields
        (field (name "MANUFACTURER_PART_NUMBER") "LQW18AN")
        (field (name "MANUFACTURER_PART_NUMBER (PART 2: VALUE)") "15N")
      )
      (libsource (lib "Inductance 0603") (part "LQW18AN...G8ZD"))
    )
    (comp (ref "L40")
      (value "LQW18AN...G8ZD")
      (footprint ":IND 0603 (1608)")
      (fields
        (field (name "MANUFACTURER_PART_NUMBER") "LQW18AN")
        (field (name "MANUFACTURER_PART_NUMBER (PART 2: VALUE)") "33N")
      )
      (libsource (lib "Inductance 0603") (part "LQW18AN...G8ZD"))
    )
    (comp (ref "L41")
      (value "100nH")
      (footprint ":IND 0402")
      (description "Unshielded Multilayer Inductor 0402 5%")
      (fields (field (name "MANUFACTURER_PART_NUMBER") "LQG15HNR10J02D"))
      (libsource (lib "Inductance 0402") (part "LQG15HNR10J02D"))
    )
    (comp (ref "L42")
      (value "100nH")
      (footprint ":IND 0402")
      (description "Unshielded Multilayer Inductor 0402 5%")
      (fields (field (name "MANUFACTURER_PART_NUMBER") "LQG15HNR10J02D"))
      (libsource (lib "Inductance 0402") (part "LQG15HNR10J02D"))
    )
    (comp (ref "L43")
      (value "100nH")
      (footprint ":IND 0402")
      (description "Unshielded Multilayer Inductor 0402 5%")
      (fields (field (name "MANUFACTURER_PART_NUMBER") "LQG15HNR10J02D"))
      (libsource (lib "Inductance 0402") (part "LQG15HNR10J02D"))
    )
    (comp (ref "L44")
      (value "100nH")
      (footprint ":IND 0402")
      (description "Unshielded Multilayer Inductor 0402 5%")
      (fields (field (name "MANUFACTURER_PART_NUMBER") "LQG15HNR10J02D"))
      (libsource (lib "Inductance 0402") (part "LQG15HNR10J02D"))
    )
    (comp (ref "L45")
      (value "100nH")
      (footprint ":IND 0402")
      (description "Unshielded Multilayer Inductor 0402 5%")
      (fields (field (name "MANUFACTURER_PART_NUMBER") "LQG15HNR10J02D"))
      (libsource (lib "") (part "LQG15HNR10J02D_1"))
    )
    (comp (ref "R82")
      (value "RC0402FR-07")
      (footprint ":RES0402")
      (fields (field (name "MANUFACTURER_PART_NUMBER (PART 2: VALUE)") "100R"))
      (libsource (lib "Resistors 0402") (part "RC0402FR-07"))
    )
    (comp (ref "R83")
      (value "RC0402FR-07")
      (footprint ":RES0402")
      (fields (field (name "MANUFACTURER_PART_NUMBER (PART 2: VALUE)") "100R"))
      (libsource (lib "Resistors 0402") (part "RC0402FR-07"))
    )
    (comp (ref "R84")
      (value "RC0402FR-07")
      (footprint ":RES0402")
      (fields (field (name "MANUFACTURER_PART_NUMBER (PART 2: VALUE)") "12K"))
      (libsource (lib "") (part "RC0402FR-07_1"))
    )
    (comp (ref "R85")
      (value "RC0402FR-07")
      (footprint ":RES0402")
      (fields (field (name "MANUFACTURER_PART_NUMBER (PART 2: VALUE)") "10K"))
      (libsource (lib "") (part "RC0402FR-07_1"))
    )
    (comp (ref "R86")
      (value "49R9")
      (footprint ":RES0805")
      (description "49.9 Ohms ±1% 0.125W, 1/8W Chip Resistor 0805 (2012 Metric) Automotive AEC-Q200 Thick Film")
      (fields
        (field (name "MANUFACTURER_PART_NUMBER") "ERJ-6ENF49R9V")
        (field (name "MOUSER PART NUMBER") "667-ERJ-6ENF49R9V")
      )
      (libsource (lib "Resistors 0805") (part "ERJ-6ENF49R9V"))
    )
    (comp (ref "R87")
      (value "RC0402FR-07")
      (footprint ":RES0402")
      (fields (field (name "MANUFACTURER_PART_NUMBER (PART 2: VALUE)") "100R"))
      (libsource (lib "Resistors 0402") (part "RC0402FR-07"))
    )
    (comp (ref "R88")
      (value "RC0402FR-07")
      (footprint ":RES0402")
      (fields (field (name "MANUFACTURER_PART_NUMBER (PART 2: VALUE)") "100R"))
      (libsource (lib "Resistors 0402") (part "RC0402FR-07"))
    )
    (comp (ref "R89")
      (value "RC0402FR-07")
      (footprint ":RES0402")
      (fields (field (name "MANUFACTURER_PART_NUMBER (PART 2: VALUE)") "100R"))
      (libsource (lib "Resistors 0402") (part "RC0402FR-07"))
    )
    (comp (ref "R90")
      (value "RC0402FR-07")
      (footprint ":RES0402")
      (fields (field (name "MANUFACTURER_PART_NUMBER (PART 2: VALUE)") "100R"))
      (libsource (lib "Resistors 0402") (part "RC0402FR-07"))
    )
    (comp (ref "R91")
      (value "RC0402FR-07")
      (footprint ":RES0402")
      (fields (field (name "MANUFACTURER_PART_NUMBER (PART 2: VALUE)") "100R"))
      (libsource (lib "Resistors 0402") (part "RC0402FR-07"))
    )
    (comp (ref "R92")
      (value "RC0402FR-07")
      (footprint ":RES0402")
      (fields (field (name "MANUFACTURER_PART_NUMBER (PART 2: VALUE)") "100R"))
      (libsource (lib "Resistors 0402") (part "RC0402FR-07"))
    )
    (comp (ref "R93")
      (value "RC0402FR-07")
      (footprint ":RES0402")
      (fields (field (name "MANUFACTURER_PART_NUMBER (PART 2: VALUE)") "100R"))
      (libsource (lib "Resistors 0402") (part "RC0402FR-07"))
    )
    (comp (ref "R94")
      (value "RC0402FR-07")
      (footprint ":RES0402")
      (fields (field (name "MANUFACTURER_PART_NUMBER (PART 2: VALUE)") "100R"))
      (libsource (lib "Resistors 0402") (part "RC0402FR-07"))
    )
  )
  (nets
    (net (code "1") (name "+3V3") (class "Default")
      (node (ref "L41") (pin "1") (pinfunction "1_1") (pintype "passive"))
      (node (ref "L42") (pin "1") (pinfunction "1_1") (pintype "passive"))
      (node (ref "L43") (pin "1") (pinfunction "1_1") (pintype "passive"))
      (node (ref "L7") (pin "1") (pinfunction "1_1") (pintype "passive"))
      (node (ref "L8") (pin "1") (pinfunction "1_1") (pintype "passive"))
      (node (ref "L9") (pin "1") (pinfunction "1_1") (pintype "passive"))
    )
    (net (code "2") (name "/+10V5") (class "Default")
      (node (ref "FB16") (pin "2") (pinfunction "2_2") (pintype "passive"))
    )
    (net (code "3") (name "/-5V") (class "Default")
      (node (ref "R85") (pin "2") (pinfunction "2_2") (pintype "passive"))
    )
    (net (code "4") (name "/IC1_V1") (class "Default")
      (node (ref "L10") (pin "1") (pinfunction "1_1") (pintype "passive"))
    )
    (net (code "5") (name "/IC2_V1") (class "Default")
      (node (ref "L19") (pin "1") (pinfunction "1_1") (pintype "passive"))
    )
    (net (code "6") (name "/IC2_V2") (class "Default")
      (node (ref "L18") (pin "1") (pinfunction "1_1") (pintype "passive"))
    )
    (net (code "7") (name "/IC3_V1") (class "Default")
      (node (ref "L37") (pin "1") (pinfunction "1_1") (pintype "passive"))
    )
    (net (code "8") (name "/IC3_V2") (class "Default")
      (node (ref "L33") (pin "1") (pinfunction "1_1") (pintype "passive"))
    )
    (net (code "9") (name "/IC4_V1") (class "Default")
      (node (ref "L17") (pin "1") (pinfunction "1_1") (pintype "passive"))
    )
    (net (code "10") (name "/IC5_V1") (class "Default")
      (node (ref "L31") (pin "1") (pinfunction "1_1") (pintype "passive"))
    )
    (net (code "11") (name "/IC5_V2") (class "Default")
      (node (ref "L32") (pin "1") (pinfunction "1_1") (pintype "passive"))
    )
    (net (code "12") (name "/IC6_V1") (class "Default")
      (node (ref "L45") (pin "1") (pinfunction "1_1") (pintype "passive"))
    )
    (net (code "13") (name "/IC6_V2") (class "Default")
      (node (ref "L44") (pin "1") (pinfunction "1_1") (pintype "passive"))
    )
    (net (code "14") (name "/RFAG") (class "Default")
      (node (ref "R84") (pin "2") (pinfunction "2_2") (pintype "passive"))
    )
    (net (code "15") (name "/RFIO") (class "Default")
      (node (ref "IC13") (pin "11") (pinfunction "ANT_11") (pintype "passive"))
    )
    (net (code "16") (name "/RFI_HF") (class "Default")
      (node (ref "C107") (pin "1") (pinfunction "1_1") (pintype "passive"))
      (node (ref "L20") (pin "2") (pinfunction "2_2") (pintype "passive"))
      (node (ref "L24") (pin "1") (pinfunction "1_1") (pintype "passive"))
    )
    (net (code "17") (name "/RFI_LF") (class "Default")
      (node (ref "IC11") (pin "11") (pinfunction "RFC_11") (pintype "passive"))
    )
    (net (code "18") (name "/RFO_HF") (class "Default")
      (node (ref "C88") (pin "1") (pinfunction "1_1") (pintype "passive"))
      (node (ref "C91") (pin "1") (pinfunction "1_1") (pintype "passive"))
      (node (ref "L11") (pin "1") (pinfunction "1_1") (pintype "passive"))
    )
    (net (code "19") (name "/RFO_LF") (class "Default")
      (node (ref "IC8") (pin "11") (pinfunction "RFC_11") (pintype "passive"))
    )
    (net (code "20") (name "GND") (class "Default")
      (node (ref "C100") (pin "2") (pinfunction "2_2") (pintype "passive"))
      (node (ref "C101") (pin "2") (pinfunction "2_2") (pintype "passive"))
      (node (ref "C102") (pin "2") (pinfunction "2_2") (pintype "passive"))
      (node (ref "C103") (pin "2") (pinfunction "2_2") (pintype "passive"))
      (node (ref "C104") (pin "2") (pinfunction "2_2") (pintype "passive"))
      (node (ref "C105") (pin "1") (pinfunction "1_1") (pintype "passive"))
      (node (ref "C107") (pin "2") (pinfunction "2_2") (pintype "passive"))
      (node (ref "C108") (pin "2") (pinfunction "2_2") (pintype "passive"))
      (node (ref "C109") (pin "2") (pinfunction "2_2") (pintype "passive"))
      (node (ref "C110") (pin "1") (pinfunction "1_1") (pintype "passive"))
      (node (ref "C111") (pin "2") (pinfunction "2_2") (pintype "passive"))
      (node (ref "C115") (pin "2") (pinfunction "2_2") (pintype "passive"))
      (node (ref "C116") (pin "2") (pinfunction "2_2") (pintype "passive"))
      (node (ref "C117") (pin "2") (pinfunction "2_2") (pintype "passive"))
      (node (ref "C118") (pin "2") (pinfunction "2_2") (pintype "passive"))
      (node (ref "C119") (pin "1") (pinfunction "1_1") (pintype "passive"))
      (node (ref "C121") (pin "2") (pinfunction "2_2") (pintype "passive"))
      (node (ref "C122") (pin "2") (pinfunction "2_2") (pintype "passive"))
      (node (ref "C123") (pin "2") (pinfunction "2_2") (pintype "passive"))
      (node (ref "C124") (pin "2") (pinfunction "2_2") (pintype "passive"))
      (node (ref "C125") (pin "2") (pinfunction "2_2") (pintype "passive"))
      (node (ref "C126") (pin "2") (pinfunction "2_2") (pintype "passive"))
      (node (ref "C130") (pin "2") (pinfunction "2_2") (pintype "passive"))
      (node (ref "C131") (pin "2") (pinfunction "2_2") (pintype "passive"))
      (node (ref "C132") (pin "2") (pinfunction "2_2") (pintype "passive"))
      (node (ref "C136") (pin "2") (pinfunction "2_2") (pintype "passive"))
      (node (ref "C137") (pin "2") (pinfunction "2_2") (pintype "passive"))
      (node (ref "C138") (pin "2") (pinfunction "2_2") (pintype "passive"))
      (node (ref "C139") (pin "2") (pinfunction "2_2") (pintype "passive"))
      (node (ref "C140") (pin "2") (pinfunction "2_2") (pintype "passive"))
      (node (ref "C141") (pin "1") (pinfunction "1_1") (pintype "passive"))
      (node (ref "C142") (pin "2") (pinfunction "2_2") (pintype "passive"))
      (node (ref "C143") (pin "1") (pinfunction "1_1") (pintype "passive"))
      (node (ref "C144") (pin "2") (pinfunction "2_2") (pintype "passive"))
      (node (ref "C145") (pin "1") (pinfunction "1_1") (pintype "passive"))
      (node (ref "C146") (pin "2") (pinfunction "2_2") (pintype "passive"))
      (node (ref "C81") (pin "2") (pinfunction "2_2") (pintype "passive"))
      (node (ref "C82") (pin "2") (pinfunction "2_2") (pintype "passive"))
      (node (ref "C83") (pin "1") (pinfunction "1_1") (pintype "passive"))
      (node (ref "C84") (pin "2") (pinfunction "2_2") (pintype "passive"))
      (node (ref "C85") (pin "1") (pinfunction "1_1") (pintype "passive"))
      (node (ref "C86") (pin "2") (pinfunction "2_2") (pintype "passive"))
      (node (ref "C87") (pin "1") (pinfunction "1_1") (pintype "passive"))
      (node (ref "C88") (pin "2") (pinfunction "2_2") (pintype "passive"))
      (node (ref "C89") (pin "2") (pinfunction "2_2") (pintype "passive"))
      (node (ref "C90") (pin "2") (pinfunction "2_2") (pintype "passive"))
      (node (ref "C94") (pin "2") (pinfunction "2_2") (pintype "passive"))
      (node (ref "C95") (pin "2") (pinfunction "2_2") (pintype "passive"))
      (node (ref "C96") (pin "2") (pinfunction "2_2") (pintype "passive"))
      (node (ref "DA1") (pin "17") (pinfunction "PAD_17") (pintype "passive"))
      (node (ref "IC10") (pin "10") (pinfunction "GND_10") (pintype "passive"))
      (node (ref "IC10") (pin "12") (pinfunction "GND_12") (pintype "passive"))
      (node (ref "IC10") (pin "14") (pinfunction "GND_14") (pintype "passive"))
      (node (ref "IC10") (pin "16") (pinfunction "GND_16") (pintype "passive"))
      (node (ref "IC10") (pin "17") (pinfunction "GND_17") (pintype "passive"))
      (node (ref "IC10") (pin "5") (pinfunction "GND_5") (pintype "passive"))
      (node (ref "IC10") (pin "7") (pinfunction "GND_7") (pintype "passive"))
      (node (ref "IC10") (pin "9") (pinfunction "GDN_9") (pintype "passive"))
      (node (ref "IC11") (pin "10") (pinfunction "GND_10") (pintype "passive"))
      (node (ref "IC11") (pin "12") (pinfunction "GND_12") (pintype "passive"))
      (node (ref "IC11") (pin "13") (pinfunction "GND_13") (pintype "passive"))
      (node (ref "IC11") (pin "14") (pinfunction "GND_14") (pintype "passive"))
      (node (ref "IC11") (pin "16") (pinfunction "GND_16") (pintype "passive"))
      (node (ref "IC11") (pin "17") (pinfunction "GND_17") (pintype "passive"))
      (node (ref "IC11") (pin "4") (pinfunction "V2_4") (pintype "power_in"))
      (node (ref "IC11") (pin "5") (pinfunction "GND_5") (pintype "passive"))
      (node (ref "IC11") (pin "7") (pinfunction "GND_7") (pintype "passive"))
      (node (ref "IC11") (pin "8") (pinfunction "GND_8") (pintype "passive"))
      (node (ref "IC11") (pin "9") (pinfunction "GDN_9") (pintype "passive"))
      (node (ref "IC12") (pin "10") (pinfunction "GND_10") (pintype "passive"))
      (node (ref "IC12") (pin "12") (pinfunction "GND_12") (pintype "passive"))
      (node (ref "IC12") (pin "14") (pinfunction "GND_14") (pintype "passive"))
      (node (ref "IC12") (pin "16") (pinfunction "GND_16") (pintype "passive"))
      (node (ref "IC12") (pin "17") (pinfunction "GND_17") (pintype "passive"))
      (node (ref "IC12") (pin "5") (pinfunction "GND_5") (pintype "passive"))
      (node (ref "IC12") (pin "7") (pinfunction "GND_7") (pintype "passive"))
      (node (ref "IC12") (pin "9") (pinfunction "GDN_9") (pintype "passive"))
      (node (ref "IC13") (pin "10") (pinfunction "GND_10") (pintype "passive"))
      (node (ref "IC13") (pin "12") (pinfunction "GND_12") (pintype "passive"))
      (node (ref "IC13") (pin "14") (pinfunction "GND_14") (pintype "passive"))
      (node (ref "IC13") (pin "16") (pinfunction "GND_16") (pintype "passive"))
      (node (ref "IC13") (pin "17") (pinfunction "GND_17") (pintype "passive"))
      (node (ref "IC13") (pin "5") (pinfunction "GND_5") (pintype "passive"))
      (node (ref "IC13") (pin "7") (pinfunction "GND_7") (pintype "passive"))
      (node (ref "IC13") (pin "9") (pinfunction "GDN_9") (pintype "passive"))
      (node (ref "IC8") (pin "10") (pinfunction "GND_10") (pintype "passive"))
      (node (ref "IC8") (pin "12") (pinfunction "GND_12") (pintype "passive"))
      (node (ref "IC8") (pin "13") (pinfunction "GND_13") (pintype "passive"))
      (node (ref "IC8") (pin "14") (pinfunction "GND_14") (pintype "passive"))
      (node (ref "IC8") (pin "16") (pinfunction "GND_16") (pintype "passive"))
      (node (ref "IC8") (pin "17") (pinfunction "GND_17") (pintype "passive"))
      (node (ref "IC8") (pin "4") (pinfunction "V2_4") (pintype "power_in"))
      (node (ref "IC8") (pin "5") (pinfunction "GND_5") (pintype "passive"))
      (node (ref "IC8") (pin "7") (pinfunction "GND_7") (pintype "passive"))
      (node (ref "IC8") (pin "8") (pinfunction "GND_8") (pintype "passive"))
      (node (ref "IC8") (pin "9") (pinfunction "GDN_9") (pintype "passive"))
      (node (ref "IC9") (pin "10") (pinfunction "GND_10") (pintype "passive"))
      (node (ref "IC9") (pin "12") (pinfunction "GND_12") (pintype "passive"))
      (node (ref "IC9") (pin "14") (pinfunction "GND_14") (pintype "passive"))
      (node (ref "IC9") (pin "16") (pinfunction "GND_16") (pintype "passive"))
      (node (ref "IC9") (pin "17") (pinfunction "GND_17") (pintype "passive"))
      (node (ref "IC9") (pin "5") (pinfunction "GND_5") (pintype "passive"))
      (node (ref "IC9") (pin "7") (pinfunction "GND_7") (pintype "passive"))
      (node (ref "IC9") (pin "9") (pinfunction "GDN_9") (pintype "passive"))
      (node (ref "L20") (pin "1") (pinfunction "1_1") (pintype "passive"))
      (node (ref "L21") (pin "1") (pinfunction "1_1") (pintype "passive"))
      (node (ref "L22") (pin "1") (pinfunction "1_1") (pintype "passive"))
      (node (ref "L27") (pin "1") (pinfunction "1_1") (pintype "passive"))
      (node (ref "L28") (pin "1") (pinfunction "1_1") (pintype "passive"))
      (node (ref "L29") (pin "1") (pinfunction "1_1") (pintype "passive"))
    )
    (net (code "21") (name "Net-(C81-Pad1)") (class "Default")
      (node (ref "C81") (pin "1") (pinfunction "1_1") (pintype "passive"))
      (node (ref "L10") (pin "2") (pinfunction "2_2") (pintype "passive"))
      (node (ref "R82") (pin "1") (pinfunction "1_1") (pintype "passive"))
    )
    (net (code "22") (name "Net-(C91-Pad2)") (class "Default")
      (node (ref "C91") (pin "2") (pinfunction "2_2") (pintype "passive"))
      (node (ref "C94") (pin "1") (pinfunction "1_1") (pintype "passive"))
      (node (ref "C97") (pin "1") (pinfunction "1_1") (pintype "passive"))
      (node (ref "L11") (pin "2") (pinfunction "2_2") (pintype "passive"))
      (node (ref "L14") (pin "1") (pinfunction "1_1") (pintype "passive"))
    )
    (net (code "23") (name "Net-(C92-Pad2)") (class "Default")
      (node (ref "C92") (pin "2") (pinfunction "2_2") (pintype "passive"))
      (node (ref "C95") (pin "1") (pinfunction "1_1") (pintype "passive"))
      (node (ref "C98") (pin "1") (pinfunction "1_1") (pintype "passive"))
      (node (ref "L12") (pin "2") (pinfunction "2_2") (pintype "passive"))
      (node (ref "L15") (pin "1") (pinfunction "1_1") (pintype "passive"))
    )
    (net (code "24") (name "Net-(C93-Pad2)") (class "Default")
      (node (ref "C93") (pin "2") (pinfunction "2_2") (pintype "passive"))
      (node (ref "C96") (pin "1") (pinfunction "1_1") (pintype "passive"))
      (node (ref "C99") (pin "1") (pinfunction "1_1") (pintype "passive"))
      (node (ref "L13") (pin "2") (pinfunction "2_2") (pintype "passive"))
      (node (ref "L16") (pin "1") (pinfunction "1_1") (pintype "passive"))
    )
    (net (code "25") (name "Net-(C100-Pad1)") (class "Default")
      (node (ref "C100") (pin "1") (pinfunction "1_1") (pintype "passive"))
      (node (ref "L17") (pin "2") (pinfunction "2_2") (pintype "passive"))
      (node (ref "R83") (pin "1") (pinfunction "1_1") (pintype "passive"))
    )
    (net (code "26") (name "Net-(C104-Pad1)") (class "Default")
      (node (ref "C104") (pin "1") (pinfunction "1_1") (pintype "passive"))
      (node (ref "L18") (pin "2") (pinfunction "2_2") (pintype "passive"))
      (node (ref "R87") (pin "1") (pinfunction "1_1") (pintype "passive"))
    )
    (net (code "27") (name "Net-(C105-Pad2)") (class "Default")
      (node (ref "C105") (pin "2") (pinfunction "2_2") (pintype "passive"))
      (node (ref "R84") (pin "1") (pinfunction "1_1") (pintype "passive"))
      (node (ref "R85") (pin "1") (pinfunction "1_1") (pintype "passive"))
      (node (ref "R86") (pin "1") (pinfunction "1_1") (pintype "passive"))
    )
    (net (code "28") (name "Net-(C106-Pad2)") (class "Default")
      (node (ref "C106") (pin "2") (pinfunction "2_2") (pintype "passive"))
      (node (ref "DA1") (pin "2") (pinfunction "RFIN_2") (pintype "passive"))
      (node (ref "DA1") (pin "3") (pinfunction "RFIN_3") (pintype "passive"))
      (node (ref "L23") (pin "1") (pinfunction "1_1") (pintype "passive"))
    )
    (net (code "29") (name "Net-(C110-Pad2)") (class "Default")
      (node (ref "C110") (pin "2") (pinfunction "2_2") (pintype "passive"))
      (node (ref "L23") (pin "2") (pinfunction "2_2") (pintype "passive"))
      (node (ref "R86") (pin "2") (pinfunction "2_2") (pintype "passive"))
    )
    (net (code "30") (name "Net-(C111-Pad1)") (class "Default")
      (node (ref "C111") (pin "1") (pinfunction "1_1") (pintype "passive"))
      (node (ref "L19") (pin "2") (pinfunction "2_2") (pintype "passive"))
      (node (ref "R88") (pin "1") (pinfunction "1_1") (pintype "passive"))
    )
    (net (code "31") (name "Net-(C112-Pad1)") (class "Default")
      (node (ref "C112") (pin "1") (pinfunction "1_1") (pintype "passive"))
      (node (ref "L24") (pin "2") (pinfunction "2_2") (pintype "passive"))
    )
    (net (code "32") (name "Net-(C113-Pad1)") (class "Default")
      (node (ref "C113") (pin "1") (pinfunction "1_1") (pintype "passive"))
      (node (ref "L25") (pin "2") (pinfunction "2_2") (pintype "passive"))
    )
    (net (code "33") (name "Net-(C114-Pad1)") (class "Default")
      (node (ref "C114") (pin "1") (pinfunction "1_1") (pintype "passive"))
      (node (ref "L26") (pin "2") (pinfunction "2_2") (pintype "passive"))
    )
    (net (code "34") (name "Net-(C115-Pad1)") (class "Default")
      (node (ref "C115") (pin "1") (pinfunction "1_1") (pintype "passive"))
      (node (ref "L31") (pin "2") (pinfunction "2_2") (pintype "passive"))
      (node (ref "R89") (pin "1") (pinfunction "1_1") (pintype "passive"))
    )
    (net (code "35") (name "Net-(C119-Pad2)") (class "Default")
      (node (ref "C119") (pin "2") (pinfunction "2_2") (pintype "passive"))
      (node (ref "FB16") (pin "1") (pinfunction "1_1") (pintype "passive"))
      (node (ref "L30") (pin "2") (pinfunction "2_2") (pintype "passive"))
    )
    (net (code "36") (name "Net-(C120-Pad1)") (class "Default")
      (node (ref "C120") (pin "1") (pinfunction "1_1") (pintype "passive"))
      (node (ref "DA1") (pin "10") (pinfunction "RFOUT_10") (pintype "passive"))
      (node (ref "DA1") (pin "11") (pinfunction "RFOUT_11") (pintype "passive"))
      (node (ref "L30") (pin "1") (pinfunction "1_1") (pintype "passive"))
    )
    (net (code "37") (name "Net-(C121-Pad1)") (class "Default")
      (node (ref "C121") (pin "1") (pinfunction "1_1") (pintype "passive"))
      (node (ref "L32") (pin "2") (pinfunction "2_2") (pintype "passive"))
      (node (ref "R90") (pin "1") (pinfunction "1_1") (pintype "passive"))
    )
    (net (code "38") (name "Net-(C122-Pad1)") (class "Default")
      (node (ref "C122") (pin "1") (pinfunction "1_1") (pintype "passive"))
      (node (ref "L33") (pin "2") (pinfunction "2_2") (pintype "passive"))
      (node (ref "R91") (pin "1") (pinfunction "1_1") (pintype "passive"))
    )
    (net (code "39") (name "Net-(C126-Pad1)") (class "Default")
      (node (ref "C126") (pin "1") (pinfunction "1_1") (pintype "passive"))
      (node (ref "L37") (pin "2") (pinfunction "2_2") (pintype "passive"))
      (node (ref "R92") (pin "1") (pinfunction "1_1") (pintype "passive"))
    )
    (net (code "40") (name "Net-(C127-Pad2)") (class "Default")
      (node (ref "C127") (pin "2") (pinfunction "2_2") (pintype "passive"))
      (node (ref "C130") (pin "1") (pinfunction "1_1") (pintype "passive"))
      (node (ref "C133") (pin "1") (pinfunction "1_1") (pintype "passive"))
      (node (ref "L34") (pin "2") (pinfunction "2_2") (pintype "passive"))
      (node (ref "L38") (pin "1") (pinfunction "1_1") (pintype "passive"))
    )
    (net (code "41") (name "Net-(C128-Pad2)") (class "Default")
      (node (ref "C128") (pin "2") (pinfunction "2_2") (pintype "passive"))
      (node (ref "C131") (pin "1") (pinfunction "1_1") (pintype "passive"))
      (node (ref "C134") (pin "1") (pinfunction "1_1") (pintype "passive"))
      (node (ref "L35") (pin "2") (pinfunction "2_2") (pintype "passive"))
      (node (ref "L39") (pin "1") (pinfunction "1_1") (pintype "passive"))
    )
    (net (code "42") (name "Net-(C129-Pad2)") (class "Default")
      (node (ref "C129") (pin "2") (pinfunction "2_2") (pintype "passive"))
      (node (ref "C132") (pin "1") (pinfunction "1_1") (pintype "passive"))
      (node (ref "C135") (pin "1") (pinfunction "1_1") (pintype "passive"))
      (node (ref "L36") (pin "2") (pinfunction "2_2") (pintype "passive"))
      (node (ref "L40") (pin "1") (pinfunction "1_1") (pintype "passive"))
    )
    (net (code "43") (name "Net-(C139-Pad1)") (class "Default")
      (node (ref "C139") (pin "1") (pinfunction "1_1") (pintype "passive"))
      (node (ref "L44") (pin "2") (pinfunction "2_2") (pintype "passive"))
      (node (ref "R93") (pin "1") (pinfunction "1_1") (pintype "passive"))
    )
    (net (code "44") (name "Net-(C146-Pad1)") (class "Default")
      (node (ref "C146") (pin "1") (pinfunction "1_1") (pintype "passive"))
      (node (ref "L45") (pin "2") (pinfunction "2_2") (pintype "passive"))
      (node (ref "R94") (pin "1") (pinfunction "1_1") (pintype "passive"))
    )
    (net (code "45") (name "Net-(IC8A-RF1)") (class "Default")
      (node (ref "C90") (pin "1") (pinfunction "1_1") (pintype "passive"))
      (node (ref "C93") (pin "1") (pinfunction "1_1") (pintype "passive"))
      (node (ref "IC8") (pin "15") (pinfunction "RF1_15") (pintype "passive"))
      (node (ref "L13") (pin "1") (pinfunction "1_1") (pintype "passive"))
    )
    (net (code "46") (name "Net-(IC8A-RF2)") (class "Default")
      (node (ref "C89") (pin "1") (pinfunction "1_1") (pintype "passive"))
      (node (ref "C92") (pin "1") (pinfunction "1_1") (pintype "passive"))
      (node (ref "IC8") (pin "6") (pinfunction "RF2_6") (pintype "passive"))
      (node (ref "L12") (pin "1") (pinfunction "1_1") (pintype "passive"))
    )
    (net (code "47") (name "Net-(IC8A-V1)") (class "Default")
      (node (ref "IC8") (pin "3") (pinfunction "V1_3") (pintype "passive"))
      (node (ref "R82") (pin "2") (pinfunction "2_2") (pintype "passive"))
    )
    (net (code "48") (name "Net-(IC8B-VCP)") (class "Default")
      (node (ref "C82") (pin "1") (pinfunction "1_1") (pintype "passive"))
      (node (ref "IC8") (pin "1") (pinfunction "VCP_1") (pintype "passive"))
    )
    (net (code "49") (name "Net-(IC8B-VDD)") (class "Default")
      (node (ref "C83") (pin "2") (pinfunction "2_2") (pintype "passive"))
      (node (ref "IC8") (pin "2") (pinfunction "VDD_2") (pintype "passive"))
      (node (ref "L7") (pin "2") (pinfunction "2_2") (pintype "passive"))
    )
    (net (code "50") (name "Net-(IC9A-ANT)") (class "Default")
      (node (ref "C106") (pin "1") (pinfunction "1_1") (pintype "passive"))
      (node (ref "IC9") (pin "11") (pinfunction "ANT_11") (pintype "passive"))
    )
    (net (code "51") (name "Net-(IC9A-RF1)") (class "Default")
      (node (ref "C101") (pin "1") (pinfunction "1_1") (pintype "passive"))
      (node (ref "C97") (pin "2") (pinfunction "2_2") (pintype "passive"))
      (node (ref "IC9") (pin "13") (pinfunction "RF1_13") (pintype "passive"))
      (node (ref "L14") (pin "2") (pinfunction "2_2") (pintype "passive"))
    )
    (net (code "52") (name "Net-(IC9A-RF3)") (class "Default")
      (node (ref "C103") (pin "1") (pinfunction "1_1") (pintype "passive"))
      (node (ref "C99") (pin "2") (pinfunction "2_2") (pintype "passive"))
      (node (ref "IC9") (pin "8") (pinfunction "RF3_8") (pintype "passive"))
      (node (ref "L16") (pin "2") (pinfunction "2_2") (pintype "passive"))
    )
    (net (code "53") (name "Net-(IC9A-RF4)") (class "Default")
      (node (ref "C102") (pin "1") (pinfunction "1_1") (pintype "passive"))
      (node (ref "C98") (pin "2") (pinfunction "2_2") (pintype "passive"))
      (node (ref "IC9") (pin "6") (pinfunction "RF4_6") (pintype "passive"))
      (node (ref "L15") (pin "2") (pinfunction "2_2") (pintype "passive"))
    )
    (net (code "54") (name "Net-(IC9A-V1)") (class "Default")
      (node (ref "IC9") (pin "3") (pinfunction "V1_3") (pintype "passive"))
      (node (ref "R88") (pin "2") (pinfunction "2_2") (pintype "passive"))
    )
    (net (code "55") (name "Net-(IC9A-V2)") (class "Default")
      (node (ref "IC9") (pin "4") (pinfunction "V2_4") (pintype "power_in"))
      (node (ref "R87") (pin "2") (pinfunction "2_2") (pintype "passive"))
    )
    (net (code "56") (name "Net-(IC9B-VCP)") (class "Default")
      (node (ref "C84") (pin "1") (pinfunction "1_1") (pintype "passive"))
      (node (ref "IC9") (pin "1") (pinfunction "VCP_1") (pintype "passive"))
    )
    (net (code "57") (name "Net-(IC9B-VDD)") (class "Default")
      (node (ref "C85") (pin "2") (pinfunction "2_2") (pintype "passive"))
      (node (ref "IC9") (pin "2") (pinfunction "VDD_2") (pintype "passive"))
      (node (ref "L8") (pin "2") (pinfunction "2_2") (pintype "passive"))
    )
    (net (code "58") (name "Net-(IC10A-ANT)") (class "Default")
      (node (ref "IC10") (pin "11") (pinfunction "ANT_11") (pintype "passive"))
      (node (ref "IC13") (pin "15") (pinfunction "RF2_15") (pintype "passive"))
    )
    (net (code "59") (name "Net-(IC10A-RF1)") (class "Default")
      (node (ref "C114") (pin "2") (pinfunction "2_2") (pintype "passive"))
      (node (ref "C118") (pin "1") (pinfunction "1_1") (pintype "passive"))
      (node (ref "IC10") (pin "13") (pinfunction "RF1_13") (pintype "passive"))
      (node (ref "L29") (pin "2") (pinfunction "2_2") (pintype "passive"))
    )
    (net (code "60") (name "Net-(IC10A-RF2)") (class "Default")
      (node (ref "C113") (pin "2") (pinfunction "2_2") (pintype "passive"))
      (node (ref "C117") (pin "1") (pinfunction "1_1") (pintype "passive"))
      (node (ref "IC10") (pin "15") (pinfunction "RF2_15") (pintype "passive"))
      (node (ref "L28") (pin "2") (pinfunction "2_2") (pintype "passive"))
    )
    (net (code "61") (name "Net-(IC10A-RF4)") (class "Default")
      (node (ref "C112") (pin "2") (pinfunction "2_2") (pintype "passive"))
      (node (ref "C116") (pin "1") (pinfunction "1_1") (pintype "passive"))
      (node (ref "IC10") (pin "6") (pinfunction "RF4_6") (pintype "passive"))
      (node (ref "L27") (pin "2") (pinfunction "2_2") (pintype "passive"))
    )
    (net (code "62") (name "Net-(IC10A-V1)") (class "Default")
      (node (ref "IC10") (pin "3") (pinfunction "V1_3") (pintype "passive"))
      (node (ref "R92") (pin "2") (pinfunction "2_2") (pintype "passive"))
    )
    (net (code "63") (name "Net-(IC10A-V2)") (class "Default")
      (node (ref "IC10") (pin "4") (pinfunction "V2_4") (pintype "power_in"))
      (node (ref "R91") (pin "2") (pinfunction "2_2") (pintype "passive"))
    )
    (net (code "64") (name "Net-(IC10B-VCP)") (class "Default")
      (node (ref "C86") (pin "1") (pinfunction "1_1") (pintype "passive"))
      (node (ref "IC10") (pin "1") (pinfunction "VCP_1") (pintype "passive"))
    )
    (net (code "65") (name "Net-(IC10B-VDD)") (class "Default")
      (node (ref "C87") (pin "2") (pinfunction "2_2") (pintype "passive"))
      (node (ref "IC10") (pin "2") (pinfunction "VDD_2") (pintype "passive"))
      (node (ref "L9") (pin "2") (pinfunction "2_2") (pintype "passive"))
    )
    (net (code "66") (name "Net-(IC11A-RF1)") (class "Default")
      (node (ref "C108") (pin "1") (pinfunction "1_1") (pintype "passive"))
      (node (ref "IC11") (pin "15") (pinfunction "RF1_15") (pintype "passive"))
      (node (ref "L21") (pin "2") (pinfunction "2_2") (pintype "passive"))
      (node (ref "L25") (pin "1") (pinfunction "1_1") (pintype "passive"))
    )
    (net (code "67") (name "Net-(IC11A-RF2)") (class "Default")
      (node (ref "C109") (pin "1") (pinfunction "1_1") (pintype "passive"))
      (node (ref "IC11") (pin "6") (pinfunction "RF2_6") (pintype "passive"))
      (node (ref "L22") (pin "2") (pinfunction "2_2") (pintype "passive"))
      (node (ref "L26") (pin "1") (pinfunction "1_1") (pintype "passive"))
    )
    (net (code "68") (name "Net-(IC11A-V1)") (class "Default")
      (node (ref "IC11") (pin "3") (pinfunction "V1_3") (pintype "passive"))
      (node (ref "R83") (pin "2") (pinfunction "2_2") (pintype "passive"))
    )
    (net (code "69") (name "Net-(IC11B-VCP)") (class "Default")
      (node (ref "C140") (pin "1") (pinfunction "1_1") (pintype "passive"))
      (node (ref "IC11") (pin "1") (pinfunction "VCP_1") (pintype "passive"))
    )
    (net (code "70") (name "Net-(IC11B-VDD)") (class "Default")
      (node (ref "C141") (pin "2") (pinfunction "2_2") (pintype "passive"))
      (node (ref "IC11") (pin "2") (pinfunction "VDD_2") (pintype "passive"))
      (node (ref "L41") (pin "2") (pinfunction "2_2") (pintype "passive"))
    )
    (net (code "71") (name "Net-(IC12A-ANT)") (class "Default")
      (node (ref "C120") (pin "2") (pinfunction "2_2") (pintype "passive"))
      (node (ref "IC12") (pin "11") (pinfunction "ANT_11") (pintype "passive"))
    )
    (net (code "72") (name "Net-(IC12A-RF1)") (class "Default")
      (node (ref "C125") (pin "1") (pinfunction "1_1") (pintype "passive"))
      (node (ref "C129") (pin "1") (pinfunction "1_1") (pintype "passive"))
      (node (ref "IC12") (pin "13") (pinfunction "RF1_13") (pintype "passive"))
      (node (ref "L36") (pin "1") (pinfunction "1_1") (pintype "passive"))
    )
    (net (code "73") (name "Net-(IC12A-RF3)") (class "Default")
      (node (ref "C124") (pin "1") (pinfunction "1_1") (pintype "passive"))
      (node (ref "C128") (pin "1") (pinfunction "1_1") (pintype "passive"))
      (node (ref "IC12") (pin "8") (pinfunction "RF3_8") (pintype "passive"))
      (node (ref "L35") (pin "1") (pinfunction "1_1") (pintype "passive"))
    )
    (net (code "74") (name "Net-(IC12A-RF4)") (class "Default")
      (node (ref "C123") (pin "1") (pinfunction "1_1") (pintype "passive"))
      (node (ref "C127") (pin "1") (pinfunction "1_1") (pintype "passive"))
      (node (ref "IC12") (pin "6") (pinfunction "RF4_6") (pintype "passive"))
      (node (ref "L34") (pin "1") (pinfunction "1_1") (pintype "passive"))
    )
    (net (code "75") (name "Net-(IC12A-V1)") (class "Default")
      (node (ref "IC12") (pin "3") (pinfunction "V1_3") (pintype "passive"))
      (node (ref "R89") (pin "2") (pinfunction "2_2") (pintype "passive"))
    )
    (net (code "76") (name "Net-(IC12A-V2)") (class "Default")
      (node (ref "IC12") (pin "4") (pinfunction "V2_4") (pintype "power_in"))
      (node (ref "R90") (pin "2") (pinfunction "2_2") (pintype "passive"))
    )
    (net (code "77") (name "Net-(IC12B-VCP)") (class "Default")
      (node (ref "C142") (pin "1") (pinfunction "1_1") (pintype "passive"))
      (node (ref "IC12") (pin "1") (pinfunction "VCP_1") (pintype "passive"))
    )
    (net (code "78") (name "Net-(IC12B-VDD)") (class "Default")
      (node (ref "C143") (pin "2") (pinfunction "2_2") (pintype "passive"))
      (node (ref "IC12") (pin "2") (pinfunction "VDD_2") (pintype "passive"))
      (node (ref "L42") (pin "2") (pinfunction "2_2") (pintype "passive"))
    )
    (net (code "79") (name "Net-(IC13A-RF1)") (class "Default")
      (node (ref "C133") (pin "2") (pinfunction "2_2") (pintype "passive"))
      (node (ref "C136") (pin "1") (pinfunction "1_1") (pintype "passive"))
      (node (ref "IC13") (pin "13") (pinfunction "RF1_13") (pintype "passive"))
      (node (ref "L38") (pin "2") (pinfunction "2_2") (pintype "passive"))
    )
    (net (code "80") (name "Net-(IC13A-RF3)") (class "Default")
      (node (ref "C134") (pin "2") (pinfunction "2_2") (pintype "passive"))
      (node (ref "C137") (pin "1") (pinfunction "1_1") (pintype "passive"))
      (node (ref "IC13") (pin "8") (pinfunction "RF3_8") (pintype "passive"))
      (node (ref "L39") (pin "2") (pinfunction "2_2") (pintype "passive"))
    )
    (net (code "81") (name "Net-(IC13A-RF4)") (class "Default")
      (node (ref "C135") (pin "2") (pinfunction "2_2") (pintype "passive"))
      (node (ref "C138") (pin "1") (pinfunction "1_1") (pintype "passive"))
      (node (ref "IC13") (pin "6") (pinfunction "RF4_6") (pintype "passive"))
      (node (ref "L40") (pin "2") (pinfunction "2_2") (pintype "passive"))
    )
    (net (code "82") (name "Net-(IC13A-V1)") (class "Default")
      (node (ref "IC13") (pin "3") (pinfunction "V1_3") (pintype "passive"))
      (node (ref "R94") (pin "2") (pinfunction "2_2") (pintype "passive"))
    )
    (net (code "83") (name "Net-(IC13A-V2)") (class "Default")
      (node (ref "IC13") (pin "4") (pinfunction "V2_4") (pintype "power_in"))
      (node (ref "R93") (pin "2") (pinfunction "2_2") (pintype "passive"))
    )
    (net (code "84") (name "Net-(IC13B-VCP)") (class "Default")
      (node (ref "C144") (pin "1") (pinfunction "1_1") (pintype "passive"))
      (node (ref "IC13") (pin "1") (pinfunction "VCP_1") (pintype "passive"))
    )
    (net (code "85") (name "Net-(IC13B-VDD)") (class "Default")
      (node (ref "C145") (pin "2") (pinfunction "2_2") (pintype "passive"))
      (node (ref "IC13") (pin "2") (pinfunction "VDD_2") (pintype "passive"))
      (node (ref "L43") (pin "2") (pinfunction "2_2") (pintype "passive"))
    )
    (net (code "86") (name "unconnected-(IC9A-RF2-Pad15)") (class "Default")
      (node (ref "IC9") (pin "15") (pinfunction "RF2_15") (pintype "passive"))
    )
    (net (code "87") (name "unconnected-(IC10A-RF3-Pad8)") (class "Default")
      (node (ref "IC10") (pin "8") (pinfunction "RF3_8") (pintype "passive"))
    )
    (net (code "88") (name "unconnected-(IC12A-RF2-Pad15)") (class "Default")
      (node (ref "IC12") (pin "15") (pinfunction "RF2_15") (pintype "passive"))
    )
  )
)
